# Shift_Registers.net
KiCad netlist of a schematic drawn in EAGLE
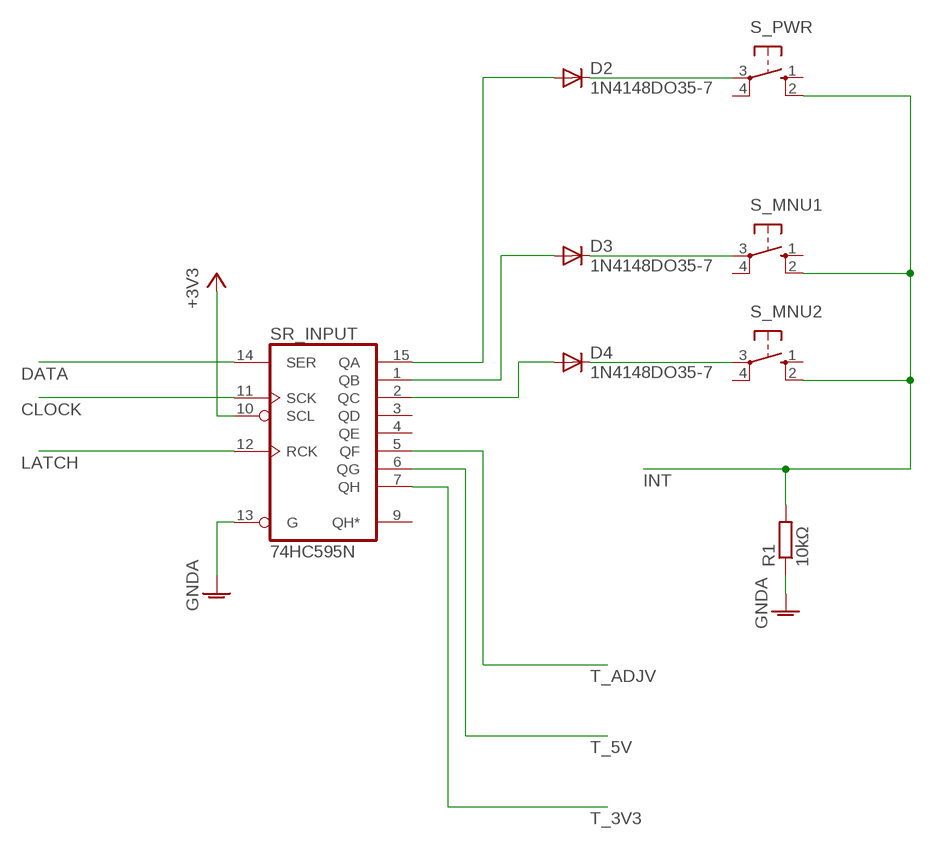
[diagram p0: schematic, sheet 1]

(export (version "E")
  (design (tool "Eeschema 10.0.6"))
  (components
    (comp (ref "D2")
      (value "1N4148DO35-7")
      (footprint "eagle-import:DO35-7")
      (libsource (lib "eagle-import") (part "1N4148DO35-7"))
    )
    (comp (ref "D3")
      (value "1N4148DO35-7")
      (footprint "eagle-import:DO35-7")
      (libsource (lib "eagle-import") (part "1N4148DO35-7"))
    )
    (comp (ref "D4")
      (value "1N4148DO35-7")
      (footprint "eagle-import:DO35-7")
      (libsource (lib "eagle-import") (part "1N4148DO35-7"))
    )
    (comp (ref "R1")
      (value "10kΩ")
      (footprint "eagle-import:0207_10")
      (libsource (lib "eagle-import") (part "R-EU_0207/10"))
    )
    (comp (ref "SR_INPUT")
      (value "74HC595N")
      (footprint "eagle-import:DIL16")
      (libsource (lib "eagle-import") (part "74595NHC"))
    )
    (comp (ref "S_MNU1")
      (value "10-XX")
      (footprint "eagle-import:B3F-10XX")
      (fields (field (name "MPN") "B3F-1000"))
      (libsource (lib "eagle-import") (part "10-XX"))
    )
    (comp (ref "S_MNU2")
      (value "10-XX")
      (footprint "eagle-import:B3F-10XX")
      (fields (field (name "MPN") "B3F-1000"))
      (libsource (lib "eagle-import") (part "10-XX"))
    )
    (comp (ref "S_PWR")
      (value "10-XX")
      (footprint "eagle-import:B3F-10XX")
      (fields (field (name "MPN") "B3F-1000"))
      (libsource (lib "eagle-import") (part "10-XX"))
    )
  )
  (nets
    (net (code "1") (name "+3V3") (class "Default")
      (node (ref "SR_INPUT") (pin "10") (pinfunction "SCL_10") (pintype "input"))
    )
    (net (code "2") (name "/CLOCK") (class "Default")
      (node (ref "SR_INPUT") (pin "11") (pinfunction "SCK_11") (pintype "input"))
    )
    (net (code "3") (name "/DATA") (class "Default")
      (node (ref "SR_INPUT") (pin "14") (pinfunction "SER_14") (pintype "input"))
    )
    (net (code "4") (name "/INT") (class "Default")
      (node (ref "R1") (pin "2") (pinfunction "2_2") (pintype "passive"))
      (node (ref "S_MNU1") (pin "2") (pinfunction "S1_2") (pintype "passive"))
      (node (ref "S_MNU2") (pin "2") (pinfunction "S1_2") (pintype "passive"))
      (node (ref "S_PWR") (pin "2") (pinfunction "S1_2") (pintype "passive"))
    )
    (net (code "5") (name "/LATCH") (class "Default")
      (node (ref "SR_INPUT") (pin "12") (pinfunction "RCK_12") (pintype "input"))
    )
    (net (code "6") (name "/T_3V3") (class "Default")
      (node (ref "SR_INPUT") (pin "7") (pinfunction "QH_7") (pintype "tri_state"))
    )
    (net (code "7") (name "/T_5V") (class "Default")
      (node (ref "SR_INPUT") (pin "6") (pinfunction "QG_6") (pintype "tri_state"))
    )
    (net (code "8") (name "/T_ADJV") (class "Default")
      (node (ref "SR_INPUT") (pin "5") (pinfunction "QF_5") (pintype "tri_state"))
    )
    (net (code "9") (name "GNDA") (class "Default")
      (node (ref "R1") (pin "1") (pinfunction "1_1") (pintype "passive"))
      (node (ref "SR_INPUT") (pin "13") (pinfunction "G_13") (pintype "input"))
    )
    (net (code "10") (name "Net-(SR_INPUTA-QA)") (class "Default")
      (node (ref "D2") (pin "A") (pinfunction "A_A") (pintype "passive"))
      (node (ref "SR_INPUT") (pin "15") (pinfunction "QA_15") (pintype "tri_state"))
    )
    (net (code "11") (name "Net-(SR_INPUTA-QB)") (class "Default")
      (node (ref "D3") (pin "A") (pinfunction "A_A") (pintype "passive"))
      (node (ref "SR_INPUT") (pin "1") (pinfunction "QB_1") (pintype "tri_state"))
    )
    (net (code "12") (name "Net-(SR_INPUTA-QC)") (class "Default")
      (node (ref "D4") (pin "A") (pinfunction "A_A") (pintype "passive"))
      (node (ref "SR_INPUT") (pin "2") (pinfunction "QC_2") (pintype "tri_state"))
    )
    (net (code "13") (name "Net-(S_MNU1-P)") (class "Default")
      (node (ref "D3") (pin "C") (pinfunction "C_C") (pintype "passive"))
      (node (ref "S_MNU1") (pin "3") (pinfunction "P_3") (pintype "passive"))
    )
    (net (code "14") (name "Net-(S_MNU2-P)") (class "Default")
      (node (ref "D4") (pin "C") (pinfunction "C_C") (pintype "passive"))
      (node (ref "S_MNU2") (pin "3") (pinfunction "P_3") (pintype "passive"))
    )
    (net (code "15") (name "Net-(S_PWR-P)") (class "Default")
      (node (ref "D2") (pin "C") (pinfunction "C_C") (pintype "passive"))
      (node (ref "S_PWR") (pin "3") (pinfunction "P_3") (pintype "passive"))
    )
    (net (code "16") (name "unconnected-(SR_INPUTA-QD-Pad3)") (class "Default")
      (node (ref "SR_INPUT") (pin "3") (pinfunction "QD_3") (pintype "tri_state"))
    )
    (net (code "17") (name "unconnected-(SR_INPUTA-QE-Pad4)") (class "Default")
      (node (ref "SR_INPUT") (pin "4") (pinfunction "QE_4") (pintype "tri_state"))
    )
    (net (code "18") (name "unconnected-(SR_INPUTA-QH*-Pad9)") (class "Default")
      (node (ref "SR_INPUT") (pin "9") (pinfunction "QH*_9") (pintype "tri_state"))
    )
    (net (code "19") (name "unconnected-(S_MNU1-P1-Pad4)") (class "Default")
      (node (ref "S_MNU1") (pin "4") (pinfunction "P1_4") (pintype "passive"))
    )
    (net (code "20") (name "unconnected-(S_MNU1-S-Pad1)") (class "Default")
      (node (ref "S_MNU1") (pin "1") (pinfunction "S_1") (pintype "passive"))
    )
    (net (code "21") (name "unconnected-(S_MNU2-P1-Pad4)") (class "Default")
      (node (ref "S_MNU2") (pin "4") (pinfunction "P1_4") (pintype "passive"))
    )
    (net (code "22") (name "unconnected-(S_MNU2-S-Pad1)") (class "Default")
      (node (ref "S_MNU2") (pin "1") (pinfunction "S_1") (pintype "passive"))
    )
    (net (code "23") (name "unconnected-(S_PWR-P1-Pad4)") (class "Default")
      (node (ref "S_PWR") (pin "4") (pinfunction "P1_4") (pintype "passive"))
    )
    (net (code "24") (name "unconnected-(S_PWR-S-Pad1)") (class "Default")
      (node (ref "S_PWR") (pin "1") (pinfunction "S_1") (pintype "passive"))
    )
  )
)
